# SimpleSwitchPirLightCO2_RFM69W.net
KiCad netlist of a schematic drawn in EAGLE
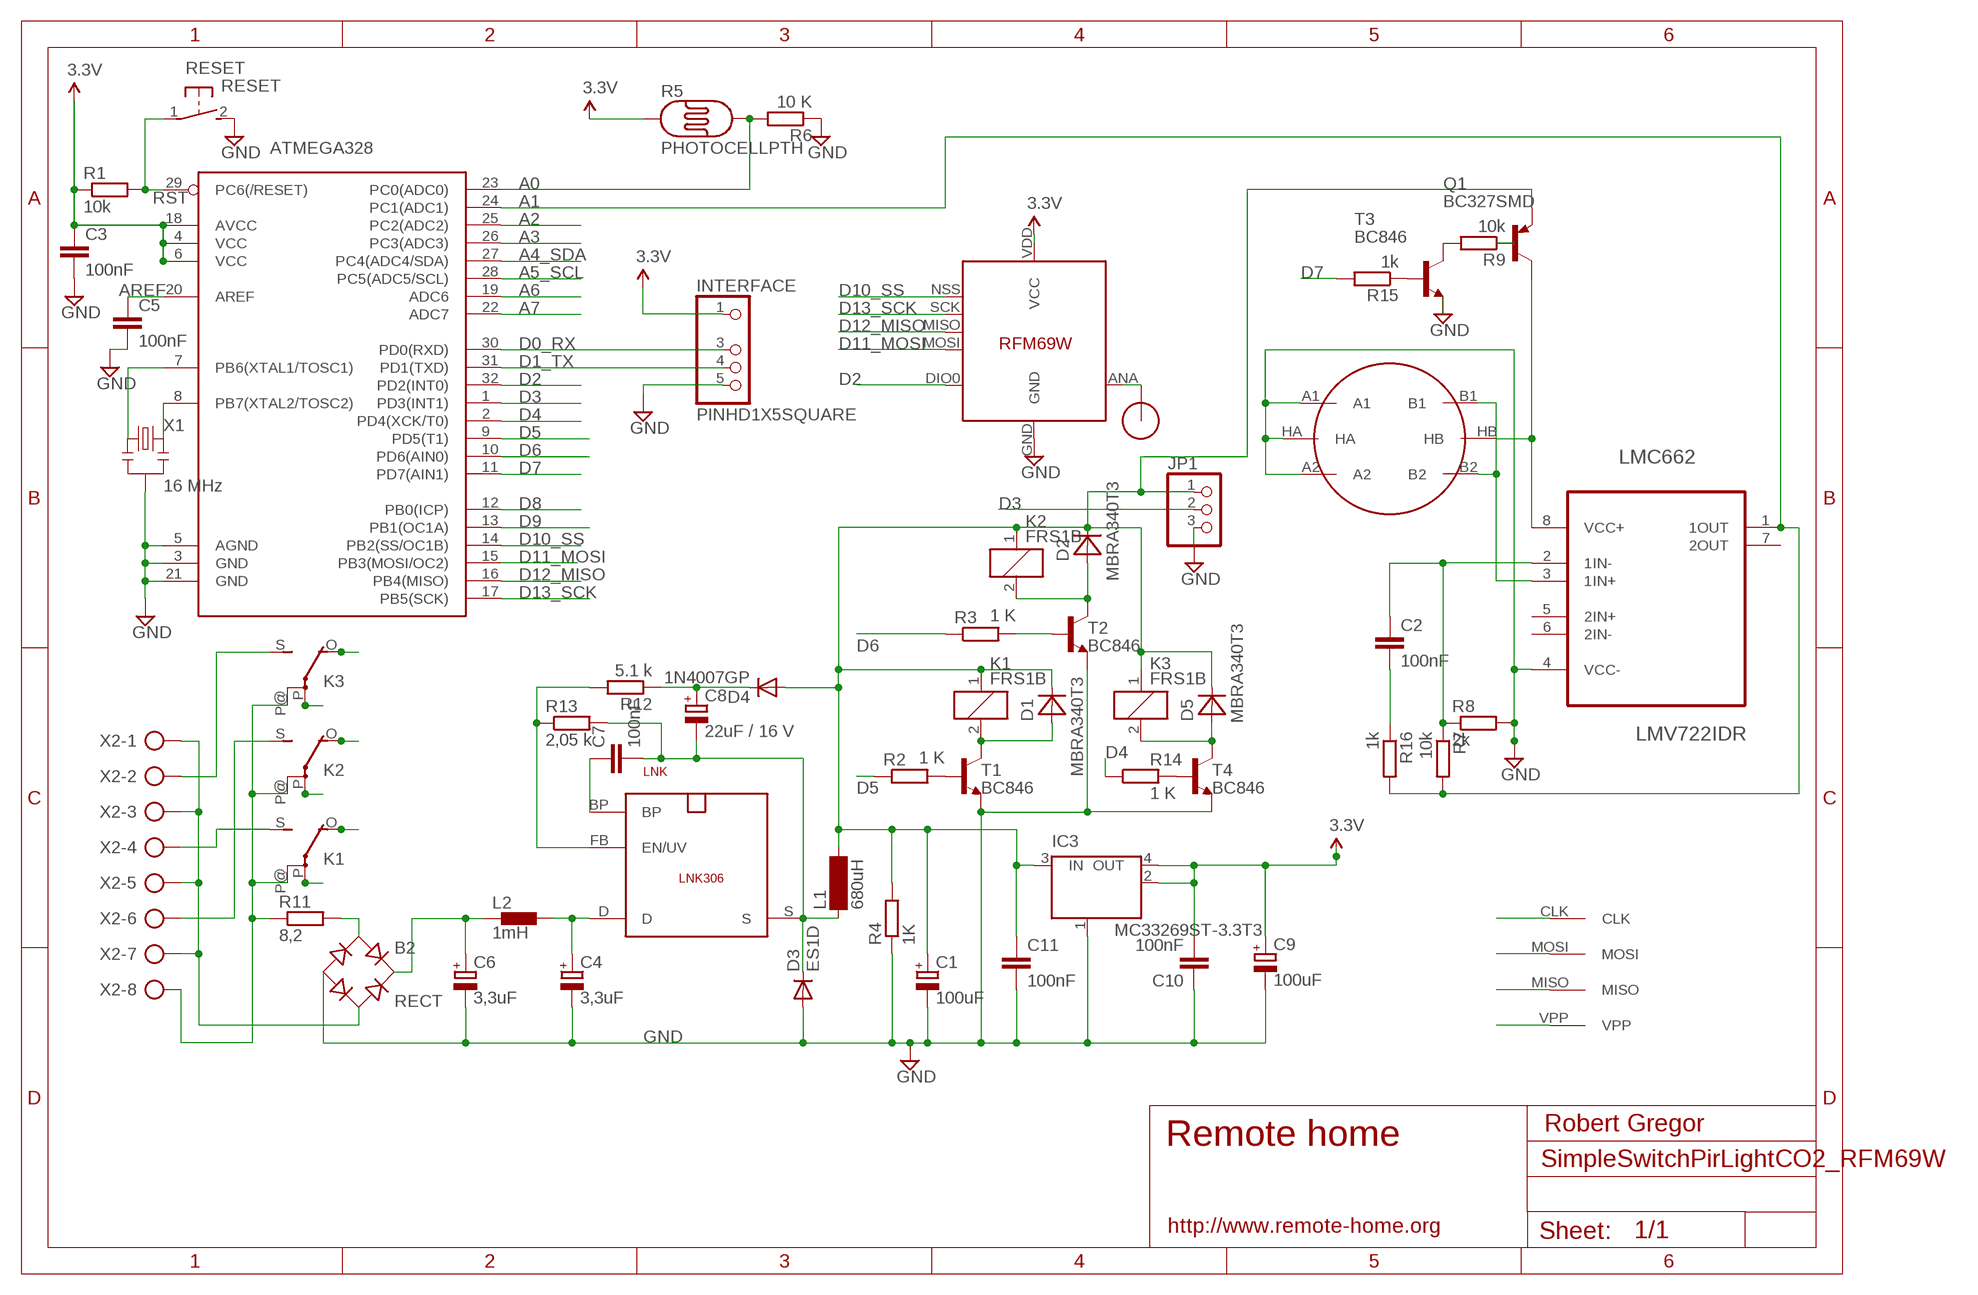
[diagram p0: schematic, sheet 1]

(export (version "E")
  (design (tool "Eeschema 10.0.6"))
  (components
    (comp (ref "ATMEGA328")
      (value "ATMega-328")
      (footprint "eagle-import:TQFP32-08")
      (libsource (lib "eagle-import") (part "ATMEGA168/328TQFP32"))
    )
    (comp (ref "B2")
      (value "RECT")
      (footprint "eagle-import:TO-269AA")
      (libsource (lib "eagle-import") (part "RECTIFIER-S40"))
    )
    (comp (ref "C1")
      (value "100uF")
      (footprint "eagle-import:SMC_B")
      (libsource (lib "eagle-import") (part "CPOL-EUSMCB"))
    )
    (comp (ref "C2")
      (value "100nF")
      (footprint "eagle-import:C2012")
      (libsource (lib "eagle-import") (part "C-EUC2012"))
    )
    (comp (ref "C3")
      (value "100nF")
      (footprint "eagle-import:C2012")
      (libsource (lib "eagle-import") (part "C-EUC2012"))
    )
    (comp (ref "C4")
      (value "3,3uF")
      (footprint "eagle-import:E5-10,5")
      (libsource (lib "eagle-import") (part "CPOL-EUE5-10.5"))
    )
    (comp (ref "C5")
      (value "100nF")
      (footprint "eagle-import:C2012")
      (libsource (lib "eagle-import") (part "C-EUC2012"))
    )
    (comp (ref "C6")
      (value "3,3uF")
      (footprint "eagle-import:E5-10,5")
      (libsource (lib "eagle-import") (part "CPOL-EUE5-10.5"))
    )
    (comp (ref "C7")
      (value "100nF")
      (footprint "eagle-import:C2012")
      (libsource (lib "eagle-import") (part "C-EUC2012"))
    )
    (comp (ref "C8")
      (value "22uF / 16 V")
      (footprint "eagle-import:SMC_C")
      (libsource (lib "eagle-import") (part "CPOL-EUSMCC"))
    )
    (comp (ref "C9")
      (value "100uF")
      (footprint "eagle-import:SMC_B")
      (libsource (lib "eagle-import") (part "CPOL-EUSMCB"))
    )
    (comp (ref "C10")
      (value "100nF")
      (footprint "eagle-import:C2012")
      (libsource (lib "eagle-import") (part "C-EUC2012"))
    )
    (comp (ref "C11")
      (value "100nF")
      (footprint "eagle-import:C2012")
      (libsource (lib "eagle-import") (part "C-EUC2012"))
    )
    (comp (ref "D1")
      (value "MBRA340T3")
      (footprint "eagle-import:SMA")
      (libsource (lib "eagle-import") (part "MBRA340T3"))
    )
    (comp (ref "D2")
      (value "MBRA340T3")
      (footprint "eagle-import:SMA")
      (libsource (lib "eagle-import") (part "MBRA340T3"))
    )
    (comp (ref "D3")
      (value "ES1D")
      (footprint "eagle-import:DO214AC")
      (libsource (lib "eagle-import") (part "DIODE-DO214AC"))
    )
    (comp (ref "D4")
      (value "1N4007GP")
      (footprint "eagle-import:DO214AA")
      (libsource (lib "eagle-import") (part "DIODE-DO214AA"))
    )
    (comp (ref "D5")
      (value "MBRA340T3")
      (footprint "eagle-import:SMA")
      (libsource (lib "eagle-import") (part "MBRA340T3"))
    )
    (comp (ref "IC3")
      (value "MC33269ST-3.3T3")
      (footprint "eagle-import:SOT223")
      (libsource (lib "eagle-import") (part "MC33269ST-3.3T3"))
    )
    (comp (ref "INTERFACE")
      (value "PINHD1X5SQUARE")
      (footprint "eagle-import:PINHD1X05-SQUARE")
      (libsource (lib "eagle-import") (part "PINHD1X5SQUARE"))
    )
    (comp (ref "JP1")
      (value "PINHD-1X03_2.54-S")
      (footprint "eagle-import:1X03-S")
      (libsource (lib "eagle-import") (part "PINHD-1X03_2.54-S"))
    )
    (comp (ref "K1")
      (value "FRS1B")
      (footprint "eagle-import:FRS1B")
      (libsource (lib "eagle-import") (part "FRS1B"))
    )
    (comp (ref "K2")
      (value "FRS1B")
      (footprint "eagle-import:FRS1B")
      (libsource (lib "eagle-import") (part "FRS1B"))
    )
    (comp (ref "K3")
      (value "FRS1B")
      (footprint "eagle-import:FRS1B")
      (libsource (lib "eagle-import") (part "FRS1B"))
    )
    (comp (ref "L1")
      (value "680uH")
      (footprint "eagle-import:BS11")
      (libsource (lib "eagle-import") (part "BS11"))
    )
    (comp (ref "L2")
      (value "1mH")
      (footprint "eagle-import:BL02RN1")
      (libsource (lib "eagle-import") (part "BL02RN1"))
    )
    (comp (ref "LMC662")
      (value "LMV722IDR")
      (footprint "eagle-import:SOIC127P600X175-8N")
      (libsource (lib "eagle-import") (part "LMV722IDR"))
    )
    (comp (ref "LNK")
      (value "LNK306")
      (footprint "eagle-import:SO-8C")
      (libsource (lib "eagle-import") (part "SO-8C"))
    )
    (comp (ref "Q1")
      (value "BC327SMD")
      (footprint "eagle-import:SOT23-BEC")
      (libsource (lib "eagle-import") (part "BC327SMD"))
    )
    (comp (ref "R1")
      (value "10k")
      (footprint "eagle-import:R2012")
      (libsource (lib "eagle-import") (part "R-EU_R2012"))
    )
    (comp (ref "R2")
      (value "1 K")
      (footprint "eagle-import:M2012")
      (libsource (lib "eagle-import") (part "R-EU_M2012"))
    )
    (comp (ref "R3")
      (value "1 K")
      (footprint "eagle-import:M2012")
      (libsource (lib "eagle-import") (part "R-EU_M2012"))
    )
    (comp (ref "R4")
      (value "1K")
      (footprint "eagle-import:M2012")
      (libsource (lib "eagle-import") (part "R-EU_M2012"))
    )
    (comp (ref "R5")
      (value "PHOTOCELLPTH")
      (footprint "eagle-import:PHOTOCELL")
      (libsource (lib "eagle-import") (part "PHOTOCELLPTH"))
    )
    (comp (ref "R6")
      (value "10 K")
      (footprint "eagle-import:M2012")
      (libsource (lib "eagle-import") (part "R-EU_M2012"))
    )
    (comp (ref "R7")
      (value "10k")
      (footprint "eagle-import:R2012")
      (libsource (lib "eagle-import") (part "R-EU_R2012"))
    )
    (comp (ref "R8")
      (value "2k")
      (footprint "eagle-import:R2012")
      (libsource (lib "eagle-import") (part "R-EU_R2012"))
    )
    (comp (ref "R9")
      (value "10k")
      (footprint "eagle-import:R2012")
      (libsource (lib "eagle-import") (part "R-EU_R2012"))
    )
    (comp (ref "R11")
      (value "8,2")
      (footprint "eagle-import:0411_12")
      (libsource (lib "eagle-import") (part "R-EU_0411/12"))
    )
    (comp (ref "R12")
      (value "5.1 k")
      (footprint "eagle-import:M2012")
      (libsource (lib "eagle-import") (part "R-EU_M2012"))
    )
    (comp (ref "R13")
      (value "2,05 k")
      (footprint "eagle-import:M2012")
      (libsource (lib "eagle-import") (part "R-EU_M2012"))
    )
    (comp (ref "R14")
      (value "1 K")
      (footprint "eagle-import:M2012")
      (libsource (lib "eagle-import") (part "R-EU_M2012"))
    )
    (comp (ref "R15")
      (value "1k")
      (footprint "eagle-import:R2012")
      (libsource (lib "eagle-import") (part "R-EU_R2012"))
    )
    (comp (ref "R16")
      (value "1k")
      (footprint "eagle-import:R2012")
      (libsource (lib "eagle-import") (part "R-EU_R2012"))
    )
    (comp (ref "RESET")
      (value "RESET")
      (footprint "eagle-import:DTSM-3")
      (libsource (lib "eagle-import") (part "DTSM-3"))
    )
    (comp (ref "RFM69")
      (value "RFM69W")
      (footprint "eagle-import:RFM69W")
      (libsource (lib "eagle-import") (part "RFM69W"))
    )
    (comp (ref "T1")
      (value "BC846")
      (footprint "eagle-import:SOT23")
      (libsource (lib "eagle-import") (part "BC846"))
    )
    (comp (ref "T2")
      (value "BC846")
      (footprint "eagle-import:SOT23")
      (libsource (lib "eagle-import") (part "BC846"))
    )
    (comp (ref "T3")
      (value "BC846")
      (footprint "eagle-import:SOT23")
      (libsource (lib "eagle-import") (part "BC846"))
    )
    (comp (ref "T4")
      (value "BC846")
      (footprint "eagle-import:SOT23")
      (libsource (lib "eagle-import") (part "BC846"))
    )
    (comp (ref "U$1")
      (value "RFM12B_ANTENNA")
      (footprint "eagle-import:RFM12B-ANTENNA")
      (libsource (lib "eagle-import") (part "RFM12B_ANTENNA"))
    )
    (comp (ref "U$2")
      (value "AVRHEADERDIP")
      (footprint "eagle-import:AVRHEADER")
      (libsource (lib "eagle-import") (part "AVRHEADERDIP"))
    )
    (comp (ref "U$4")
      (value "METHANE_SENSOR")
      (footprint "eagle-import:MQ-3")
      (libsource (lib "eagle-import") (part "METHANE_SENSOR"))
    )
    (comp (ref "X1")
      (value "16 MHz")
      (footprint "eagle-import:RESONATOR-SMD")
      (libsource (lib "eagle-import") (part "RESONATORSMD"))
    )
    (comp (ref "X2")
      (value "AK500/8")
      (footprint "eagle-import:AK500_8")
      (libsource (lib "eagle-import") (part "AK500/8"))
    )
  )
  (nets
    (net (code "1") (name "/A0") (class "Default")
      (node (ref "ATMEGA328") (pin "23") (pinfunction "PC0(ADC0)_23") (pintype "bidirectional"))
      (node (ref "R5") (pin "2") (pinfunction "P$2_2") (pintype "bidirectional"))
      (node (ref "R6") (pin "2") (pinfunction "2_2") (pintype "passive"))
    )
    (net (code "2") (name "/A1") (class "Default")
      (node (ref "ATMEGA328") (pin "24") (pinfunction "PC1(ADC1)_24") (pintype "bidirectional"))
      (node (ref "LMC662") (pin "1") (pinfunction "1OUT_1") (pintype "output"))
      (node (ref "R16") (pin "2") (pinfunction "2_2") (pintype "passive"))
      (node (ref "R7") (pin "2") (pinfunction "2_2") (pintype "passive"))
    )
    (net (code "3") (name "/A2") (class "Default")
      (node (ref "ATMEGA328") (pin "25") (pinfunction "PC2(ADC2)_25") (pintype "bidirectional"))
    )
    (net (code "4") (name "/A3") (class "Default")
      (node (ref "ATMEGA328") (pin "26") (pinfunction "PC3(ADC3)_26") (pintype "bidirectional"))
    )
    (net (code "5") (name "/A4_SDA") (class "Default")
      (node (ref "ATMEGA328") (pin "27") (pinfunction "PC4(ADC4/SDA)_27") (pintype "bidirectional"))
    )
    (net (code "6") (name "/A5_SCL") (class "Default")
      (node (ref "ATMEGA328") (pin "28") (pinfunction "PC5(ADC5/SCL)_28") (pintype "bidirectional"))
    )
    (net (code "7") (name "/A6") (class "Default")
      (node (ref "ATMEGA328") (pin "19") (pinfunction "ADC6_19") (pintype "bidirectional"))
    )
    (net (code "8") (name "/A7") (class "Default")
      (node (ref "ATMEGA328") (pin "22") (pinfunction "ADC7_22") (pintype "bidirectional"))
    )
    (net (code "9") (name "/AREF") (class "Default")
      (node (ref "ATMEGA328") (pin "20") (pinfunction "AREF_20") (pintype "bidirectional"))
      (node (ref "C5") (pin "1") (pinfunction "1_1") (pintype "passive"))
    )
    (net (code "10") (name "/D0_RX") (class "Default")
      (node (ref "ATMEGA328") (pin "30") (pinfunction "PD0(RXD)_30") (pintype "bidirectional"))
      (node (ref "INTERFACE") (pin "3") (pinfunction "3_3") (pintype "passive"))
    )
    (net (code "11") (name "/D1_TX") (class "Default")
      (node (ref "ATMEGA328") (pin "31") (pinfunction "PD1(TXD)_31") (pintype "bidirectional"))
      (node (ref "INTERFACE") (pin "4") (pinfunction "4_4") (pintype "passive"))
    )
    (net (code "12") (name "/D2") (class "Default")
      (node (ref "ATMEGA328") (pin "32") (pinfunction "PD2(INT0)_32") (pintype "bidirectional"))
      (node (ref "RFM69") (pin "DIO0") (pinfunction "DIO0_DIO0") (pintype "open_collector"))
    )
    (net (code "13") (name "/D3") (class "Default")
      (node (ref "ATMEGA328") (pin "1") (pinfunction "PD3(INT1)_1") (pintype "bidirectional"))
      (node (ref "JP1") (pin "2") (pinfunction "2_2") (pintype "passive"))
    )
    (net (code "14") (name "/D4") (class "Default")
      (node (ref "ATMEGA328") (pin "2") (pinfunction "PD4(XCK/T0)_2") (pintype "bidirectional"))
      (node (ref "R14") (pin "1") (pinfunction "1_1") (pintype "passive"))
    )
    (net (code "15") (name "/D5") (class "Default")
      (node (ref "ATMEGA328") (pin "9") (pinfunction "PD5(T1)_9") (pintype "bidirectional"))
      (node (ref "R2") (pin "1") (pinfunction "1_1") (pintype "passive"))
    )
    (net (code "16") (name "/D6") (class "Default")
      (node (ref "ATMEGA328") (pin "10") (pinfunction "PD6(AIN0)_10") (pintype "bidirectional"))
      (node (ref "R3") (pin "1") (pinfunction "1_1") (pintype "passive"))
    )
    (net (code "17") (name "/D7") (class "Default")
      (node (ref "ATMEGA328") (pin "11") (pinfunction "PD7(AIN1)_11") (pintype "bidirectional"))
      (node (ref "R15") (pin "2") (pinfunction "2_2") (pintype "passive"))
    )
    (net (code "18") (name "/D8") (class "Default")
      (node (ref "ATMEGA328") (pin "12") (pinfunction "PB0(ICP)_12") (pintype "bidirectional"))
    )
    (net (code "19") (name "/D9") (class "Default")
      (node (ref "ATMEGA328") (pin "13") (pinfunction "PB1(OC1A)_13") (pintype "bidirectional"))
    )
    (net (code "20") (name "/D10_SS") (class "Default")
      (node (ref "ATMEGA328") (pin "14") (pinfunction "PB2(SS/OC1B)_14") (pintype "bidirectional"))
      (node (ref "RFM69") (pin "NSS") (pinfunction "SEL_NSS") (pintype "input"))
    )
    (net (code "21") (name "/D11_MOSI") (class "Default")
      (node (ref "ATMEGA328") (pin "15") (pinfunction "PB3(MOSI/OC2)_15") (pintype "bidirectional"))
      (node (ref "RFM69") (pin "MOSI") (pinfunction "MOSI_MOSI") (pintype "output"))
      (node (ref "U$2") (pin "MOSI") (pinfunction "MOSI_MOSI") (pintype "bidirectional"))
    )
    (net (code "22") (name "/D12_MISO") (class "Default")
      (node (ref "ATMEGA328") (pin "16") (pinfunction "PB4(MISO)_16") (pintype "bidirectional"))
      (node (ref "RFM69") (pin "MISO") (pinfunction "MISO_MISO") (pintype "input"))
      (node (ref "U$2") (pin "MISO") (pinfunction "MISO_MISO") (pintype "bidirectional"))
    )
    (net (code "23") (name "/D13_SCK") (class "Default")
      (node (ref "ATMEGA328") (pin "17") (pinfunction "PB5(SCK)_17") (pintype "bidirectional"))
      (node (ref "RFM69") (pin "SCK") (pinfunction "SCK_SCK") (pintype "input"))
      (node (ref "U$2") (pin "CLK") (pinfunction "CLK_CLK") (pintype "bidirectional"))
    )
    (net (code "24") (name "/RST") (class "Default")
      (node (ref "ATMEGA328") (pin "29") (pinfunction "PC6(/RESET)_29") (pintype "bidirectional"))
      (node (ref "R1") (pin "2") (pinfunction "2_2") (pintype "passive"))
      (node (ref "RESET") (pin "1") (pinfunction "1_1") (pintype "passive"))
      (node (ref "U$2") (pin "VPP") (pinfunction "VPP_VPP") (pintype "bidirectional"))
    )
    (net (code "25") (name "3.3V") (class "Default")
      (node (ref "ATMEGA328") (pin "18") (pinfunction "AVCC_18") (pintype "bidirectional"))
      (node (ref "ATMEGA328") (pin "4") (pinfunction "VCC_4") (pintype "bidirectional"))
      (node (ref "ATMEGA328") (pin "6") (pinfunction "VCC_6") (pintype "bidirectional"))
      (node (ref "C10") (pin "2") (pinfunction "2_2") (pintype "passive"))
      (node (ref "C3") (pin "1") (pinfunction "1_1") (pintype "passive"))
      (node (ref "C9") (pin "+") (pinfunction "+_+") (pintype "passive"))
      (node (ref "IC3") (pin "2") (pinfunction "OUT_2") (pintype "passive"))
      (node (ref "IC3") (pin "4") (pinfunction "OUT_4") (pintype "passive"))
      (node (ref "INTERFACE") (pin "1") (pinfunction "1_1") (pintype "passive"))
      (node (ref "R1") (pin "1") (pinfunction "1_1") (pintype "passive"))
      (node (ref "R5") (pin "1") (pinfunction "P$1_1") (pintype "bidirectional"))
      (node (ref "RFM69") (pin "VDD") (pinfunction "VCC_VDD") (pintype "power_in"))
    )
    (net (code "26") (name "GND") (class "Default")
      (node (ref "ATMEGA328") (pin "21") (pinfunction "GND_21") (pintype "bidirectional"))
      (node (ref "ATMEGA328") (pin "3") (pinfunction "GND_3") (pintype "bidirectional"))
      (node (ref "ATMEGA328") (pin "5") (pinfunction "AGND_5") (pintype "bidirectional"))
      (node (ref "B2") (pin "-") (pinfunction "-_-") (pintype "passive"))
      (node (ref "C1") (pin "-") (pinfunction "-_-") (pintype "passive"))
      (node (ref "C10") (pin "1") (pinfunction "1_1") (pintype "passive"))
      (node (ref "C11") (pin "2") (pinfunction "2_2") (pintype "passive"))
      (node (ref "C3") (pin "2") (pinfunction "2_2") (pintype "passive"))
      (node (ref "C4") (pin "-") (pinfunction "-_-") (pintype "passive"))
      (node (ref "C5") (pin "2") (pinfunction "2_2") (pintype "passive"))
      (node (ref "C6") (pin "-") (pinfunction "-_-") (pintype "passive"))
      (node (ref "C9") (pin "-") (pinfunction "-_-") (pintype "passive"))
      (node (ref "D3") (pin "A") (pinfunction "A_A") (pintype "passive"))
      (node (ref "IC3") (pin "1") (pinfunction "GND/ADJ_1") (pintype "input"))
      (node (ref "INTERFACE") (pin "5") (pinfunction "5_5") (pintype "passive"))
      (node (ref "JP1") (pin "3") (pinfunction "3_3") (pintype "passive"))
      (node (ref "LMC662") (pin "4") (pinfunction "VCC-_4") (pintype "power_in"))
      (node (ref "R4") (pin "1") (pinfunction "1_1") (pintype "passive"))
      (node (ref "R6") (pin "1") (pinfunction "1_1") (pintype "passive"))
      (node (ref "R8") (pin "2") (pinfunction "2_2") (pintype "passive"))
      (node (ref "RESET") (pin "2") (pinfunction "2_2") (pintype "passive"))
      (node (ref "RFM69") (pin "GND") (pinfunction "GND_GND") (pintype "power_in"))
      (node (ref "T1") (pin "2") (pinfunction "E_2") (pintype "passive"))
      (node (ref "T2") (pin "2") (pinfunction "E_2") (pintype "passive"))
      (node (ref "T3") (pin "2") (pinfunction "E_2") (pintype "passive"))
      (node (ref "T4") (pin "2") (pinfunction "E_2") (pintype "passive"))
      (node (ref "U$4") (pin "A1") (pinfunction "A1_A1") (pintype "bidirectional"))
      (node (ref "U$4") (pin "A2") (pinfunction "A2_A2") (pintype "bidirectional"))
      (node (ref "U$4") (pin "HA") (pinfunction "HA_HA") (pintype "bidirectional"))
      (node (ref "X1") (pin "2") (pinfunction "2_2") (pintype "passive"))
    )
    (net (code "27") (name "Net-(ATMEGA328-PB6(XTAL1{slash}TOSC1))") (class "Default")
      (node (ref "ATMEGA328") (pin "7") (pinfunction "PB6(XTAL1/TOSC1)_7") (pintype "bidirectional"))
      (node (ref "X1") (pin "1") (pinfunction "1_1") (pintype "passive"))
    )
    (net (code "28") (name "Net-(ATMEGA328-PB7(XTAL2{slash}TOSC2))") (class "Default")
      (node (ref "ATMEGA328") (pin "8") (pinfunction "PB7(XTAL2/TOSC2)_8") (pintype "bidirectional"))
      (node (ref "X1") (pin "3") (pinfunction "3_3") (pintype "passive"))
    )
    (net (code "29") (name "Net-(B2-Pad+)") (class "Default")
      (node (ref "B2") (pin "+") (pinfunction "+_+") (pintype "passive"))
      (node (ref "C6") (pin "+") (pinfunction "+_+") (pintype "passive"))
      (node (ref "L2") (pin "1") (pinfunction "1_1") (pintype "passive"))
    )
    (net (code "30") (name "Net-(B2-PadAC1)") (class "Default")
      (node (ref "B2") (pin "AC1") (pinfunction "AC1_AC1") (pintype "passive"))
      (node (ref "R11") (pin "2") (pinfunction "2_2") (pintype "passive"))
    )
    (net (code "31") (name "Net-(C2-Pad2)") (class "Default")
      (node (ref "C2") (pin "2") (pinfunction "2_2") (pintype "passive"))
      (node (ref "R16") (pin "1") (pinfunction "1_1") (pintype "passive"))
    )
    (net (code "32") (name "Net-(C4-Pad+)") (class "Default")
      (node (ref "C4") (pin "+") (pinfunction "+_+") (pintype "passive"))
      (node (ref "L2") (pin "2") (pinfunction "2_2") (pintype "passive"))
      (node (ref "LNK") (pin "D") (pinfunction "D_D") (pintype "open_collector"))
    )
    (net (code "33") (name "Net-(C7-Pad1)") (class "Default")
      (node (ref "C7") (pin "1") (pinfunction "1_1") (pintype "passive"))
      (node (ref "LNK") (pin "BP") (pinfunction "BP_BP") (pintype "passive"))
    )
    (net (code "34") (name "Net-(C7-Pad2)") (class "Default")
      (node (ref "C7") (pin "2") (pinfunction "2_2") (pintype "passive"))
      (node (ref "C8") (pin "-") (pinfunction "-_-") (pintype "passive"))
      (node (ref "D3") (pin "C") (pinfunction "C_C") (pintype "passive"))
      (node (ref "L1") (pin "1") (pinfunction "1_1") (pintype "passive"))
      (node (ref "LNK") (pin "S") (pinfunction "S_S") (pintype "power_in"))
      (node (ref "R13") (pin "2") (pinfunction "2_2") (pintype "passive"))
    )
    (net (code "35") (name "Net-(C8-Pad+)") (class "Default")
      (node (ref "C8") (pin "+") (pinfunction "+_+") (pintype "passive"))
      (node (ref "D4") (pin "C") (pinfunction "C_C") (pintype "passive"))
      (node (ref "R12") (pin "1") (pinfunction "1_1") (pintype "passive"))
    )
    (net (code "36") (name "Net-(IC3-IN)") (class "Default")
      (node (ref "C1") (pin "+") (pinfunction "+_+") (pintype "passive"))
      (node (ref "C11") (pin "1") (pinfunction "1_1") (pintype "passive"))
      (node (ref "D1") (pin "C") (pinfunction "C_C") (pintype "passive"))
      (node (ref "D2") (pin "C") (pinfunction "C_C") (pintype "passive"))
      (node (ref "D4") (pin "A") (pinfunction "A_A") (pintype "passive"))
      (node (ref "D5") (pin "C") (pinfunction "C_C") (pintype "passive"))
      (node (ref "IC3") (pin "3") (pinfunction "IN_3") (pintype "input"))
      (node (ref "JP1") (pin "1") (pinfunction "1_1") (pintype "passive"))
      (node (ref "K1") (pin "1") (pinfunction "1_1") (pintype "passive"))
      (node (ref "K2") (pin "1") (pinfunction "1_1") (pintype "passive"))
      (node (ref "K3") (pin "1") (pinfunction "1_1") (pintype "passive"))
      (node (ref "L1") (pin "2") (pinfunction "2_2") (pintype "passive"))
      (node (ref "Q1") (pin "E") (pinfunction "E_E") (pintype "passive"))
      (node (ref "R4") (pin "2") (pinfunction "2_2") (pintype "passive"))
    )
    (net (code "37") (name "Net-(LMC662-1IN+)") (class "Default")
      (node (ref "LMC662") (pin "3") (pinfunction "1IN+_3") (pintype "input"))
      (node (ref "U$4") (pin "B1") (pinfunction "B1_B1") (pintype "bidirectional"))
      (node (ref "U$4") (pin "B2") (pinfunction "B2_B2") (pintype "bidirectional"))
    )
    (net (code "38") (name "Net-(LMC662-1IN-)") (class "Default")
      (node (ref "C2") (pin "1") (pinfunction "1_1") (pintype "passive"))
      (node (ref "LMC662") (pin "2") (pinfunction "1IN-_2") (pintype "input"))
      (node (ref "R7") (pin "1") (pinfunction "1_1") (pintype "passive"))
      (node (ref "R8") (pin "1") (pinfunction "1_1") (pintype "passive"))
    )
    (net (code "39") (name "Net-(LMC662-VCC+)") (class "Default")
      (node (ref "LMC662") (pin "8") (pinfunction "VCC+_8") (pintype "power_in"))
      (node (ref "Q1") (pin "C") (pinfunction "C_C") (pintype "passive"))
      (node (ref "U$4") (pin "HB") (pinfunction "HB_HB") (pintype "bidirectional"))
    )
    (net (code "40") (name "Net-(LNK-EN{slash}UV)") (class "Default")
      (node (ref "LNK") (pin "FB") (pinfunction "EN/UV_FB") (pintype "input"))
      (node (ref "R12") (pin "2") (pinfunction "2_2") (pintype "passive"))
      (node (ref "R13") (pin "1") (pinfunction "1_1") (pintype "passive"))
    )
    (net (code "41") (name "Net-(Q1-PadB)") (class "Default")
      (node (ref "Q1") (pin "B") (pinfunction "B_B") (pintype "passive"))
      (node (ref "R9") (pin "1") (pinfunction "1_1") (pintype "passive"))
    )
    (net (code "42") (name "Net-(RFM69-ANT)") (class "Default")
      (node (ref "RFM69") (pin "ANA") (pinfunction "ANT_ANA") (pintype "passive"))
      (node (ref "U$1") (pin "P$1") (pinfunction "1_P$1") (pintype "bidirectional"))
    )
    (net (code "43") (name "Net-(T1-B)") (class "Default")
      (node (ref "R2") (pin "2") (pinfunction "2_2") (pintype "passive"))
      (node (ref "T1") (pin "1") (pinfunction "B_1") (pintype "passive"))
    )
    (net (code "44") (name "Net-(T1-C)") (class "Default")
      (node (ref "D1") (pin "A") (pinfunction "A_A") (pintype "passive"))
      (node (ref "K1") (pin "2") (pinfunction "2_2") (pintype "passive"))
      (node (ref "T1") (pin "3") (pinfunction "C_3") (pintype "passive"))
    )
    (net (code "45") (name "Net-(T2-B)") (class "Default")
      (node (ref "R3") (pin "2") (pinfunction "2_2") (pintype "passive"))
      (node (ref "T2") (pin "1") (pinfunction "B_1") (pintype "passive"))
    )
    (net (code "46") (name "Net-(T2-C)") (class "Default")
      (node (ref "D2") (pin "A") (pinfunction "A_A") (pintype "passive"))
      (node (ref "K2") (pin "2") (pinfunction "2_2") (pintype "passive"))
      (node (ref "T2") (pin "3") (pinfunction "C_3") (pintype "passive"))
    )
    (net (code "47") (name "Net-(T3-B)") (class "Default")
      (node (ref "R15") (pin "1") (pinfunction "1_1") (pintype "passive"))
      (node (ref "T3") (pin "1") (pinfunction "B_1") (pintype "passive"))
    )
    (net (code "48") (name "Net-(T3-C)") (class "Default")
      (node (ref "R9") (pin "2") (pinfunction "2_2") (pintype "passive"))
      (node (ref "T3") (pin "3") (pinfunction "C_3") (pintype "passive"))
    )
    (net (code "49") (name "Net-(T4-B)") (class "Default")
      (node (ref "R14") (pin "2") (pinfunction "2_2") (pintype "passive"))
      (node (ref "T4") (pin "1") (pinfunction "B_1") (pintype "passive"))
    )
    (net (code "50") (name "Net-(T4-C)") (class "Default")
      (node (ref "D5") (pin "A") (pinfunction "A_A") (pintype "passive"))
      (node (ref "K3") (pin "2") (pinfunction "2_2") (pintype "passive"))
      (node (ref "T4") (pin "3") (pinfunction "C_3") (pintype "passive"))
    )
    (net (code "51") (name "Net-(X2A-KL)") (class "Default")
      (node (ref "B2") (pin "AC2") (pinfunction "AC2_AC2") (pintype "passive"))
      (node (ref "X2") (pin "1") (pinfunction "KL_1") (pintype "passive"))
      (node (ref "X2") (pin "3") (pinfunction "KL_3") (pintype "passive"))
      (node (ref "X2") (pin "5") (pinfunction "KL_5") (pintype "passive"))
      (node (ref "X2") (pin "7") (pinfunction "KL_7") (pintype "passive"))
    )
    (net (code "52") (name "Net-(X2B-KL)") (class "Default")
      (node (ref "K3") (pin "S") (pinfunction "S_S") (pintype "passive"))
      (node (ref "X2") (pin "2") (pinfunction "KL_2") (pintype "passive"))
    )
    (net (code "53") (name "Net-(X2D-KL)") (class "Default")
      (node (ref "K1") (pin "S") (pinfunction "S_S") (pintype "passive"))
      (node (ref "X2") (pin "4") (pinfunction "KL_4") (pintype "passive"))
    )
    (net (code "54") (name "Net-(X2F-KL)") (class "Default")
      (node (ref "K2") (pin "S") (pinfunction "S_S") (pintype "passive"))
      (node (ref "X2") (pin "6") (pinfunction "KL_6") (pintype "passive"))
    )
    (net (code "55") (name "Net-(X2H-KL)") (class "Default")
      (node (ref "K1") (pin "P@") (pinfunction "P_P@") (pintype "passive"))
      (node (ref "K2") (pin "P@") (pinfunction "P_P@") (pintype "passive"))
      (node (ref "K3") (pin "P@") (pinfunction "P_P@") (pintype "passive"))
      (node (ref "R11") (pin "1") (pinfunction "1_1") (pintype "passive"))
      (node (ref "X2") (pin "8") (pinfunction "KL_8") (pintype "passive"))
    )
    (net (code "56") (name "unconnected-(K1-PadO)") (class "Default")
      (node (ref "K1") (pin "O") (pinfunction "O_O") (pintype "passive"))
    )
    (net (code "57") (name "unconnected-(K1-PadP)") (class "Default")
      (node (ref "K1") (pin "P") (pinfunction "P_P") (pintype "passive"))
    )
    (net (code "58") (name "unconnected-(K2-PadO)") (class "Default")
      (node (ref "K2") (pin "O") (pinfunction "O_O") (pintype "passive"))
    )
    (net (code "59") (name "unconnected-(K2-PadP)") (class "Default")
      (node (ref "K2") (pin "P") (pinfunction "P_P") (pintype "passive"))
    )
    (net (code "60") (name "unconnected-(K3-PadO)") (class "Default")
      (node (ref "K3") (pin "O") (pinfunction "O_O") (pintype "passive"))
    )
    (net (code "61") (name "unconnected-(K3-PadP)") (class "Default")
      (node (ref "K3") (pin "P") (pinfunction "P_P") (pintype "passive"))
    )
    (net (code "62") (name "unconnected-(LMC662-2IN+-Pad5)") (class "Default")
      (node (ref "LMC662") (pin "5") (pinfunction "2IN+_5") (pintype "input"))
    )
    (net (code "63") (name "unconnected-(LMC662-2IN--Pad6)") (class "Default")
      (node (ref "LMC662") (pin "6") (pinfunction "2IN-_6") (pintype "input"))
    )
    (net (code "64") (name "unconnected-(LMC662-2OUT-Pad7)") (class "Default")
      (node (ref "LMC662") (pin "7") (pinfunction "2OUT_7") (pintype "output"))
    )
  )
)
